# ReproAmp_V87_Stage_v0_1.net
KiCad netlist of a schematic drawn in Altium Designer
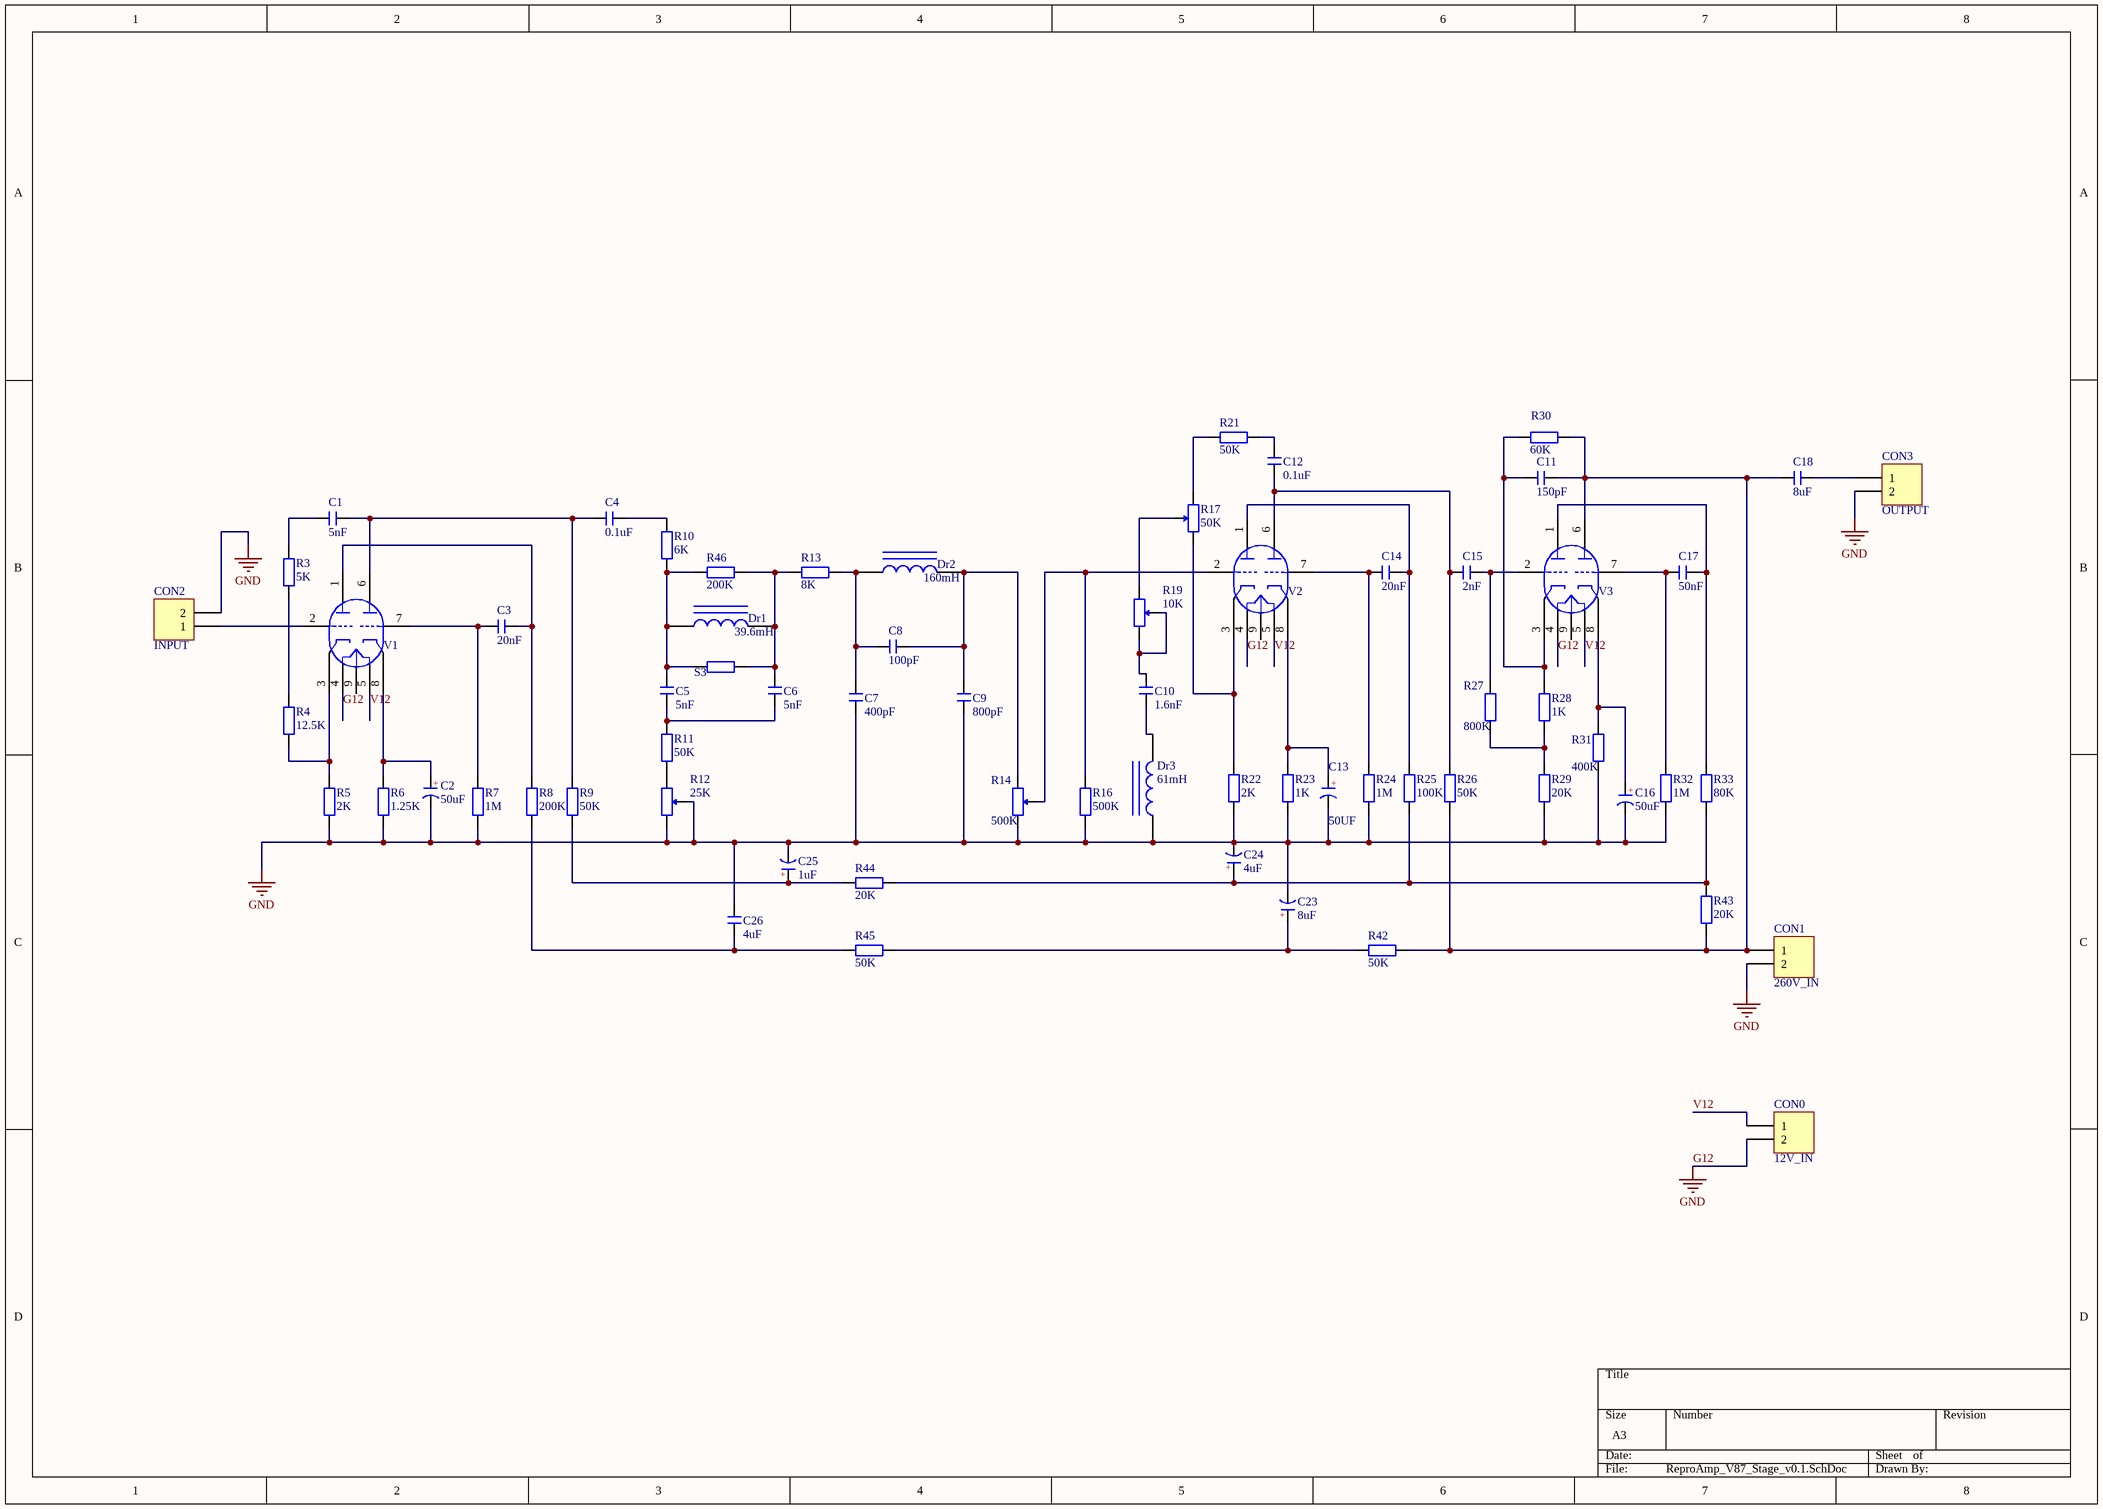
[diagram p0: ReproAmp_V87_Stage_v0.1.SchDoc]

(export (version "E")
  (design (tool "Eeschema 10.0.6"))
  (components
    (comp (ref "C1")
      (value "5nF")
      (footprint "CY 7.5*10*4")
      (description "CBB电容")
      (fields (field (name "版权归属") "源创客"))
      (libsource (lib "电阻-电容-电感") (part "C-CBB"))
    )
    (comp (ref "C2")
      (value "50uF")
      (footprint "CAP 5.0*12.5*20")
      (description "直插电解电容")
      (fields (field (name "版权归属") "源创客"))
      (libsource (lib "电阻-电容-电感") (part "C-CAP"))
    )
    (comp (ref "C3")
      (value "20nF")
      (footprint "CBB 10*12*8")
      (description "CBB电容")
      (fields (field (name "版权归属") "源创客"))
      (libsource (lib "电阻-电容-电感") (part "C-CBB"))
    )
    (comp (ref "C4")
      (value "0.1uF")
      (footprint "CBB 15*18*11")
      (description "CBB电容")
      (fields (field (name "版权归属") "源创客"))
      (libsource (lib "电阻-电容-电感") (part "C-CBB"))
    )
    (comp (ref "C5")
      (value "5nF")
      (footprint "CBB 7.2*7.2*13")
      (description "CBB电容")
      (fields (field (name "版权归属") "源创客"))
      (libsource (lib "电阻-电容-电感") (part "C-CBB"))
    )
    (comp (ref "C6")
      (value "5nF")
      (footprint "CBB 7.2*7.2*13")
      (description "CBB电容")
      (fields (field (name "版权归属") "源创客"))
      (libsource (lib "电阻-电容-电感") (part "C-CBB"))
    )
    (comp (ref "C7")
      (value "400pF")
      (footprint "CBB 7.2*7.2*13")
      (description "CBB电容")
      (fields (field (name "版权归属") "源创客"))
      (libsource (lib "电阻-电容-电感") (part "C-CBB"))
    )
    (comp (ref "C8")
      (value "100pF")
      (footprint "CBB 7.2*7.2*13")
      (description "CBB电容")
      (fields (field (name "版权归属") "源创客"))
      (libsource (lib "电阻-电容-电感") (part "C-CBB"))
    )
    (comp (ref "C9")
      (value "800pF")
      (footprint "CBB 7.2*7.2*13")
      (description "CBB电容")
      (fields (field (name "版权归属") "源创客"))
      (libsource (lib "电阻-电容-电感") (part "C-CBB"))
    )
    (comp (ref "C10")
      (value "1.6nF")
      (footprint "CBB 7.2*7.2*13")
      (description "CBB电容")
      (fields (field (name "版权归属") "源创客"))
      (libsource (lib "电阻-电容-电感") (part "C-CBB"))
    )
    (comp (ref "C11")
      (value "150pF")
      (footprint "CBB 15*18*11")
      (description "CBB电容")
      (fields (field (name "版权归属") "源创客"))
      (libsource (lib "电阻-电容-电感") (part "C-CBB"))
    )
    (comp (ref "C12")
      (value "0.1uF")
      (footprint "CBB 15*18*11")
      (description "CBB电容")
      (fields (field (name "版权归属") "源创客"))
      (libsource (lib "电阻-电容-电感") (part "C-CBB"))
    )
    (comp (ref "C13")
      (value "50UF")
      (footprint "CAP 5.0*12.5*20")
      (description "直插电解电容")
      (fields (field (name "版权归属") "源创客"))
      (libsource (lib "电阻-电容-电感") (part "C-CAP"))
    )
    (comp (ref "C14")
      (value "20nF")
      (footprint "CBB 10*12*8")
      (description "CBB电容")
      (fields (field (name "版权归属") "源创客"))
      (libsource (lib "电阻-电容-电感") (part "C-CBB"))
    )
    (comp (ref "C15")
      (value "2nF")
      (footprint "CY 7.5*8*4")
      (description "CBB电容")
      (fields (field (name "版权归属") "源创客"))
      (libsource (lib "电阻-电容-电感") (part "C-CBB"))
    )
    (comp (ref "C16")
      (value "50uF")
      (footprint "CAP 5.0*12.5*20")
      (description "直插电解电容")
      (fields (field (name "版权归属") "源创客"))
      (libsource (lib "电阻-电容-电感") (part "C-CAP"))
    )
    (comp (ref "C17")
      (value "50nF")
      (footprint "CBB 15*18*11")
      (description "CBB电容")
      (fields (field (name "版权归属") "源创客"))
      (libsource (lib "电阻-电容-电感") (part "C-CBB"))
    )
    (comp (ref "C18")
      (value "8uF")
      (footprint "CBB 50*30*30")
      (description "CBB电容")
      (fields (field (name "版权归属") "源创客"))
      (libsource (lib "电阻-电容-电感") (part "C-CBB"))
    )
    (comp (ref "C23")
      (value "8uF")
      (footprint "CAP 5.0*12.5*20")
      (description "直插电解电容")
      (fields (field (name "版权归属") "源创客"))
      (libsource (lib "电阻-电容-电感") (part "C-CAP"))
    )
    (comp (ref "C24")
      (value "4uF")
      (footprint "CAP 5.0*12.5*20")
      (description "直插电解电容")
      (fields (field (name "版权归属") "源创客"))
      (libsource (lib "电阻-电容-电感") (part "C-CAP"))
    )
    (comp (ref "C25")
      (value "1uF")
      (footprint "CAP 5.0*12.5*20")
      (description "直插电解电容")
      (fields (field (name "版权归属") "源创客"))
      (libsource (lib "电阻-电容-电感") (part "C-CAP"))
    )
    (comp (ref "C26")
      (value "4uF")
      (footprint "CBB 20*23*17")
      (description "CBB电容")
      (fields (field (name "版权归属") "源创客"))
      (libsource (lib "电阻-电容-电感") (part "C-CBB"))
    )
    (comp (ref "CON0")
      (value "12V_IN")
      (footprint "HX5.08-2L")
      (libsource (lib "Connectors") (part "EDG5.08-2P"))
    )
    (comp (ref "CON1")
      (value "260V_IN")
      (footprint "HX5.08-2L")
      (libsource (lib "Connectors") (part "EDG5.08-2P"))
    )
    (comp (ref "CON2") (value "INPUT") (footprint "HX5.08-2L") (libsource (lib "") (part "EDG5.08-2P_1")))
    (comp (ref "CON3")
      (value "OUTPUT")
      (footprint "HX5.08-2L")
      (libsource (lib "Connectors") (part "EDG5.08-2P"))
    )
    (comp (ref "Dr1")
      (value "39.6mH")
      (footprint "AXIAL-0.5")
      (description "Magnetic-Core Inductor")
      (fields (field (name "PUBLISHER") "Altium Limited"))
      (libsource (lib "Miscellaneous Devices") (part "Inductor Iron"))
    )
    (comp (ref "Dr2")
      (value "160mH")
      (footprint "AXIAL-0.5")
      (description "Magnetic-Core Inductor")
      (fields (field (name "PUBLISHER") "Altium Limited"))
      (libsource (lib "Miscellaneous Devices") (part "Inductor Iron"))
    )
    (comp (ref "Dr3")
      (value "61mH")
      (footprint "AXIAL-0.5")
      (description "Magnetic-Core Inductor")
      (fields (field (name "PUBLISHER") "Altium Limited"))
      (libsource (lib "Miscellaneous Devices") (part "Inductor Iron"))
    )
    (comp (ref "R3")
      (value "5K")
      (footprint "RS 1W")
      (description "直插色环电阻")
      (fields (field (name "版权归属") "源创客"))
      (libsource (lib "电阻-电容-电感") (part "R-CRR"))
    )
    (comp (ref "R4")
      (value "12.5K")
      (footprint "RS 1W")
      (description "直插色环电阻")
      (fields (field (name "版权归属") "源创客"))
      (libsource (lib "电阻-电容-电感") (part "R-CRR"))
    )
    (comp (ref "R5")
      (value "2K")
      (footprint "RS 1W")
      (description "直插色环电阻")
      (fields (field (name "版权归属") "源创客"))
      (libsource (lib "电阻-电容-电感") (part "R-CRR"))
    )
    (comp (ref "R6")
      (value "1.25K")
      (footprint "RS 1W")
      (description "直插色环电阻")
      (fields (field (name "版权归属") "源创客"))
      (libsource (lib "电阻-电容-电感") (part "R-CRR"))
    )
    (comp (ref "R7")
      (value "1M")
      (footprint "RS 1W")
      (description "直插色环电阻")
      (fields (field (name "版权归属") "源创客"))
      (libsource (lib "电阻-电容-电感") (part "R-CRR"))
    )
    (comp (ref "R8")
      (value "200K")
      (footprint "RS 1W")
      (description "直插色环电阻")
      (fields (field (name "版权归属") "源创客"))
      (libsource (lib "电阻-电容-电感") (part "R-CRR"))
    )
    (comp (ref "R9")
      (value "50K")
      (footprint "RS 2W")
      (description "直插色环电阻")
      (fields (field (name "版权归属") "源创客"))
      (libsource (lib "电阻-电容-电感") (part "R-CRR"))
    )
    (comp (ref "R10")
      (value "6K")
      (footprint "RS 1/2W")
      (description "直插色环电阻")
      (fields (field (name "版权归属") "源创客"))
      (libsource (lib "电阻-电容-电感") (part "R-CRR"))
    )
    (comp (ref "R11")
      (value "50K")
      (footprint "RS 1/2W")
      (description "直插色环电阻")
      (fields (field (name "版权归属") "源创客"))
      (libsource (lib "电阻-电容-电感") (part "R-CRR"))
    )
    (comp (ref "R12")
      (value "25K")
      (footprint "RS 1/2W-VR")
      (description "直插可调电阻-顶调")
      (libsource (lib "电阻-电容-电感") (part "VR-W"))
    )
    (comp (ref "R13")
      (value "8K")
      (footprint "RS 1/2W")
      (description "直插色环电阻")
      (fields (field (name "版权归属") "源创客"))
      (libsource (lib "电阻-电容-电感") (part "R-CRR"))
    )
    (comp (ref "R14")
      (value "500K")
      (footprint "RS 1/2W-VR")
      (description "直插可调电阻-顶调")
      (libsource (lib "电阻-电容-电感") (part "VR-W"))
    )
    (comp (ref "R16")
      (value "500K")
      (footprint "RS 1W")
      (description "直插色环电阻")
      (fields (field (name "版权归属") "源创客"))
      (libsource (lib "电阻-电容-电感") (part "R-CRR"))
    )
    (comp (ref "R17")
      (value "50K")
      (footprint "RS 1/2W-VR")
      (description "直插可调电阻-顶调")
      (libsource (lib "电阻-电容-电感") (part "VR-W"))
    )
    (comp (ref "R19")
      (value "10K")
      (footprint "RS 1/2W-VR")
      (description "直插可调电阻-顶调")
      (libsource (lib "电阻-电容-电感") (part "VR-W"))
    )
    (comp (ref "R21")
      (value "50K")
      (footprint "RS 1W")
      (description "直插色环电阻")
      (fields (field (name "版权归属") "源创客"))
      (libsource (lib "电阻-电容-电感") (part "R-CRR"))
    )
    (comp (ref "R22")
      (value "2K")
      (footprint "RS 1W")
      (description "直插色环电阻")
      (fields (field (name "版权归属") "源创客"))
      (libsource (lib "电阻-电容-电感") (part "R-CRR"))
    )
    (comp (ref "R23")
      (value "1K")
      (footprint "RS 1W")
      (description "直插色环电阻")
      (fields (field (name "版权归属") "源创客"))
      (libsource (lib "电阻-电容-电感") (part "R-CRR"))
    )
    (comp (ref "R24")
      (value "1M")
      (footprint "RS 1W")
      (description "直插色环电阻")
      (fields (field (name "版权归属") "源创客"))
      (libsource (lib "电阻-电容-电感") (part "R-CRR"))
    )
    (comp (ref "R25")
      (value "100K")
      (footprint "RS 2W")
      (description "直插色环电阻")
      (fields (field (name "版权归属") "源创客"))
      (libsource (lib "电阻-电容-电感") (part "R-CRR"))
    )
    (comp (ref "R26")
      (value "50K")
      (footprint "RS 1W")
      (description "直插色环电阻")
      (fields (field (name "版权归属") "源创客"))
      (libsource (lib "电阻-电容-电感") (part "R-CRR"))
    )
    (comp (ref "R27")
      (value "800K")
      (footprint "RS 1W")
      (description "直插色环电阻")
      (fields (field (name "版权归属") "源创客"))
      (libsource (lib "电阻-电容-电感") (part "R-CRR"))
    )
    (comp (ref "R28")
      (value "1K")
      (footprint "RS 1W")
      (description "直插色环电阻")
      (fields (field (name "版权归属") "源创客"))
      (libsource (lib "电阻-电容-电感") (part "R-CRR"))
    )
    (comp (ref "R29")
      (value "20K")
      (footprint "RS 1W")
      (description "直插色环电阻")
      (fields (field (name "版权归属") "源创客"))
      (libsource (lib "电阻-电容-电感") (part "R-CRR"))
    )
    (comp (ref "R30")
      (value "60K")
      (footprint "RS 1W")
      (description "直插色环电阻")
      (fields (field (name "版权归属") "源创客"))
      (libsource (lib "电阻-电容-电感") (part "R-CRR"))
    )
    (comp (ref "R31")
      (value "400K")
      (footprint "RS 1W")
      (description "直插色环电阻")
      (fields (field (name "版权归属") "源创客"))
      (libsource (lib "电阻-电容-电感") (part "R-CRR"))
    )
    (comp (ref "R32")
      (value "1M")
      (footprint "RS 1W")
      (description "直插色环电阻")
      (fields (field (name "版权归属") "源创客"))
      (libsource (lib "电阻-电容-电感") (part "R-CRR"))
    )
    (comp (ref "R33")
      (value "80K")
      (footprint "RS 2W")
      (description "直插色环电阻")
      (fields (field (name "版权归属") "源创客"))
      (libsource (lib "电阻-电容-电感") (part "R-CRR"))
    )
    (comp (ref "R42")
      (value "50K")
      (footprint "RS 1W")
      (description "直插色环电阻")
      (fields (field (name "版权归属") "源创客"))
      (libsource (lib "电阻-电容-电感") (part "R-CRR"))
    )
    (comp (ref "R43")
      (value "20K")
      (footprint "RS 1W")
      (description "直插色环电阻")
      (fields (field (name "版权归属") "源创客"))
      (libsource (lib "电阻-电容-电感") (part "R-CRR"))
    )
    (comp (ref "R44")
      (value "20K")
      (footprint "RS 1W")
      (description "直插色环电阻")
      (fields (field (name "版权归属") "源创客"))
      (libsource (lib "电阻-电容-电感") (part "R-CRR"))
    )
    (comp (ref "R45")
      (value "50K")
      (footprint "RS 1W")
      (description "直插色环电阻")
      (fields (field (name "版权归属") "源创客"))
      (libsource (lib "电阻-电容-电感") (part "R-CRR"))
    )
    (comp (ref "R46")
      (value "200K")
      (footprint "RS 1/2W")
      (description "直插色环电阻")
      (fields (field (name "版权归属") "源创客"))
      (libsource (lib "电阻-电容-电感") (part "R-CRR"))
    )
    (comp (ref "S3")
      (value "0")
      (footprint "RS 1/2W")
      (description "直插色环电阻")
      (fields (field (name "版权归属") "源创客"))
      (libsource (lib "电阻-电容-电感") (part "R-CRR"))
    )
    (comp (ref "V1")
      (value "Tube E80CC")
      (footprint "VTUBE-9")
      (description "High Mu Dual Triode")
      (fields (field (name "PUBLISHER") "Altium Limited"))
      (libsource (lib "Miscellaneous Devices") (part "Tube 12AX7"))
    )
    (comp (ref "V2")
      (value "Tube E80CC")
      (footprint "VTUBE-9")
      (description "High Mu Dual Triode")
      (fields (field (name "PUBLISHER") "Altium Limited"))
      (libsource (lib "Miscellaneous Devices") (part "Tube 12AX7"))
    )
    (comp (ref "V3")
      (value "Tube E80CC")
      (footprint "VTUBE-9")
      (description "High Mu Dual Triode")
      (fields (field (name "PUBLISHER") "Altium Limited"))
      (libsource (lib "Miscellaneous Devices") (part "Tube 12AX7"))
    )
  )
  (nets
    (net (code "1") (name "/V12") (class "Default")
      (node (ref "CON0") (pin "1") (pinfunction "1_1") (pintype "passive"))
      (node (ref "V1") (pin "5") (pinfunction "H_5") (pintype "passive"))
      (node (ref "V2") (pin "5") (pinfunction "H_5") (pintype "passive"))
      (node (ref "V3") (pin "5") (pinfunction "H_5") (pintype "passive"))
    )
    (net (code "2") (name "GND") (class "Default")
      (node (ref "C13") (pin "2") (pinfunction "K_2") (pintype "passive"))
      (node (ref "C16") (pin "2") (pinfunction "K_2") (pintype "passive"))
      (node (ref "C2") (pin "2") (pinfunction "K_2") (pintype "passive"))
      (node (ref "C23") (pin "2") (pinfunction "K_2") (pintype "passive"))
      (node (ref "C24") (pin "2") (pinfunction "K_2") (pintype "passive"))
      (node (ref "C25") (pin "2") (pinfunction "K_2") (pintype "passive"))
      (node (ref "C26") (pin "2") (pinfunction "2_2") (pintype "passive"))
      (node (ref "C7") (pin "1") (pinfunction "1_1") (pintype "passive"))
      (node (ref "C9") (pin "1") (pinfunction "1_1") (pintype "passive"))
      (node (ref "CON0") (pin "2") (pinfunction "2_2") (pintype "passive"))
      (node (ref "CON1") (pin "2") (pinfunction "2_2") (pintype "passive"))
      (node (ref "CON2") (pin "2") (pinfunction "2_2") (pintype "passive"))
      (node (ref "CON3") (pin "2") (pinfunction "2_2") (pintype "passive"))
      (node (ref "Dr3") (pin "1") (pinfunction "1_1") (pintype "passive"))
      (node (ref "R12") (pin "2") (pinfunction "2_2") (pintype "passive"))
      (node (ref "R12") (pin "3") (pinfunction "3_3") (pintype "passive"))
      (node (ref "R14") (pin "2") (pinfunction "2_2") (pintype "passive"))
      (node (ref "R16") (pin "1") (pinfunction "1_1") (pintype "passive"))
      (node (ref "R22") (pin "1") (pinfunction "1_1") (pintype "passive"))
      (node (ref "R23") (pin "1") (pinfunction "1_1") (pintype "passive"))
      (node (ref "R24") (pin "1") (pinfunction "1_1") (pintype "passive"))
      (node (ref "R29") (pin "1") (pinfunction "1_1") (pintype "passive"))
      (node (ref "R31") (pin "2") (pinfunction "2_2") (pintype "passive"))
      (node (ref "R32") (pin "2") (pinfunction "2_2") (pintype "passive"))
      (node (ref "R5") (pin "1") (pinfunction "1_1") (pintype "passive"))
      (node (ref "R6") (pin "1") (pinfunction "1_1") (pintype "passive"))
      (node (ref "R7") (pin "1") (pinfunction "1_1") (pintype "passive"))
      (node (ref "V1") (pin "4") (pinfunction "H_4") (pintype "passive"))
      (node (ref "V2") (pin "4") (pinfunction "H_4") (pintype "passive"))
      (node (ref "V3") (pin "4") (pinfunction "H_4") (pintype "passive"))
    )
    (net (code "3") (name "Net-(C1-Pad1)") (class "Default")
      (node (ref "C1") (pin "1") (pinfunction "1_1") (pintype "passive"))
      (node (ref "R3") (pin "2") (pinfunction "2_2") (pintype "passive"))
    )
    (net (code "4") (name "Net-(C2-A)") (class "Default")
      (node (ref "C2") (pin "1") (pinfunction "A_1") (pintype "passive"))
      (node (ref "R6") (pin "2") (pinfunction "2_2") (pintype "passive"))
      (node (ref "V1") (pin "8") (pinfunction "KT2_8") (pintype "passive"))
    )
    (net (code "5") (name "Net-(C4-Pad2)") (class "Default")
      (node (ref "C4") (pin "2") (pinfunction "2_2") (pintype "passive"))
      (node (ref "R10") (pin "2") (pinfunction "2_2") (pintype "passive"))
    )
    (net (code "6") (name "Net-(C5-Pad1)") (class "Default")
      (node (ref "C5") (pin "1") (pinfunction "1_1") (pintype "passive"))
      (node (ref "C6") (pin "1") (pinfunction "1_1") (pintype "passive"))
      (node (ref "R11") (pin "2") (pinfunction "2_2") (pintype "passive"))
    )
    (net (code "7") (name "Net-(C5-Pad2)") (class "Default")
      (node (ref "C5") (pin "2") (pinfunction "2_2") (pintype "passive"))
      (node (ref "Dr1") (pin "1") (pinfunction "1_1") (pintype "passive"))
      (node (ref "R10") (pin "1") (pinfunction "1_1") (pintype "passive"))
      (node (ref "R46") (pin "1") (pinfunction "1_1") (pintype "passive"))
      (node (ref "S3") (pin "1") (pinfunction "1_1") (pintype "passive"))
    )
    (net (code "8") (name "Net-(C6-Pad2)") (class "Default")
      (node (ref "C6") (pin "2") (pinfunction "2_2") (pintype "passive"))
      (node (ref "Dr1") (pin "2") (pinfunction "2_2") (pintype "passive"))
      (node (ref "R13") (pin "1") (pinfunction "1_1") (pintype "passive"))
      (node (ref "R46") (pin "2") (pinfunction "2_2") (pintype "passive"))
      (node (ref "S3") (pin "2") (pinfunction "2_2") (pintype "passive"))
    )
    (net (code "9") (name "Net-(C7-Pad2)") (class "Default")
      (node (ref "C7") (pin "2") (pinfunction "2_2") (pintype "passive"))
      (node (ref "C8") (pin "2") (pinfunction "2_2") (pintype "passive"))
      (node (ref "Dr2") (pin "1") (pinfunction "1_1") (pintype "passive"))
      (node (ref "R13") (pin "2") (pinfunction "2_2") (pintype "passive"))
    )
    (net (code "10") (name "Net-(C8-Pad1)") (class "Default")
      (node (ref "C8") (pin "1") (pinfunction "1_1") (pintype "passive"))
      (node (ref "C9") (pin "2") (pinfunction "2_2") (pintype "passive"))
      (node (ref "Dr2") (pin "2") (pinfunction "2_2") (pintype "passive"))
      (node (ref "R14") (pin "1") (pinfunction "1_1") (pintype "passive"))
    )
    (net (code "11") (name "Net-(C10-Pad1)") (class "Default")
      (node (ref "C10") (pin "1") (pinfunction "1_1") (pintype "passive"))
      (node (ref "Dr3") (pin "2") (pinfunction "2_2") (pintype "passive"))
    )
    (net (code "12") (name "Net-(C10-Pad2)") (class "Default")
      (node (ref "C10") (pin "2") (pinfunction "2_2") (pintype "passive"))
      (node (ref "R19") (pin "2") (pinfunction "2_2") (pintype "passive"))
      (node (ref "R19") (pin "3") (pinfunction "3_3") (pintype "passive"))
    )
    (net (code "13") (name "Net-(C12-Pad2)") (class "Default")
      (node (ref "C12") (pin "2") (pinfunction "2_2") (pintype "passive"))
      (node (ref "R21") (pin "2") (pinfunction "2_2") (pintype "passive"))
    )
    (net (code "14") (name "Net-(C13-A)") (class "Default")
      (node (ref "C13") (pin "1") (pinfunction "A_1") (pintype "passive"))
      (node (ref "R23") (pin "2") (pinfunction "2_2") (pintype "passive"))
      (node (ref "V2") (pin "8") (pinfunction "KT2_8") (pintype "passive"))
    )
    (net (code "15") (name "Net-(C16-A)") (class "Default")
      (node (ref "C16") (pin "1") (pinfunction "A_1") (pintype "passive"))
      (node (ref "R31") (pin "1") (pinfunction "1_1") (pintype "passive"))
      (node (ref "V3") (pin "8") (pinfunction "KT2_8") (pintype "passive"))
    )
    (net (code "16") (name "Net-(C18-Pad2)") (class "Default")
      (node (ref "C18") (pin "2") (pinfunction "2_2") (pintype "passive"))
      (node (ref "CON3") (pin "1") (pinfunction "1_1") (pintype "passive"))
    )
    (net (code "17") (name "Net-(C23-A)") (class "Default")
      (node (ref "C23") (pin "1") (pinfunction "A_1") (pintype "passive"))
      (node (ref "R42") (pin "1") (pinfunction "1_1") (pintype "passive"))
      (node (ref "R45") (pin "2") (pinfunction "2_2") (pintype "passive"))
    )
    (net (code "18") (name "Net-(C24-A)") (class "Default")
      (node (ref "C24") (pin "1") (pinfunction "A_1") (pintype "passive"))
      (node (ref "R25") (pin "1") (pinfunction "1_1") (pintype "passive"))
      (node (ref "R33") (pin "2") (pinfunction "2_2") (pintype "passive"))
      (node (ref "R43") (pin "2") (pinfunction "2_2") (pintype "passive"))
      (node (ref "R44") (pin "2") (pinfunction "2_2") (pintype "passive"))
    )
    (net (code "19") (name "Net-(C25-A)") (class "Default")
      (node (ref "C25") (pin "1") (pinfunction "A_1") (pintype "passive"))
      (node (ref "R44") (pin "1") (pinfunction "1_1") (pintype "passive"))
      (node (ref "R9") (pin "1") (pinfunction "1_1") (pintype "passive"))
    )
    (net (code "20") (name "Net-(C26-Pad1)") (class "Default")
      (node (ref "C26") (pin "1") (pinfunction "1_1") (pintype "passive"))
      (node (ref "R45") (pin "1") (pinfunction "1_1") (pintype "passive"))
      (node (ref "R8") (pin "1") (pinfunction "1_1") (pintype "passive"))
    )
    (net (code "21") (name "Net-(R3-Pad1)") (class "Default")
      (node (ref "R3") (pin "1") (pinfunction "1_1") (pintype "passive"))
      (node (ref "R4") (pin "2") (pinfunction "2_2") (pintype "passive"))
    )
    (net (code "22") (name "Net-(R11-Pad1)") (class "Default")
      (node (ref "R11") (pin "1") (pinfunction "1_1") (pintype "passive"))
      (node (ref "R12") (pin "1") (pinfunction "1_1") (pintype "passive"))
    )
    (net (code "23") (name "Net-(R17-Pad1)") (class "Default")
      (node (ref "R17") (pin "1") (pinfunction "1_1") (pintype "passive"))
      (node (ref "R21") (pin "1") (pinfunction "1_1") (pintype "passive"))
    )
    (net (code "24") (name "Net-(R17-Pad3)") (class "Default")
      (node (ref "R17") (pin "3") (pinfunction "3_3") (pintype "passive"))
      (node (ref "R19") (pin "1") (pinfunction "1_1") (pintype "passive"))
    )
    (net (code "25") (name "Net-(R27-Pad1)") (class "Default")
      (node (ref "R27") (pin "1") (pinfunction "1_1") (pintype "passive"))
      (node (ref "R28") (pin "1") (pinfunction "1_1") (pintype "passive"))
      (node (ref "R29") (pin "2") (pinfunction "2_2") (pintype "passive"))
    )
    (net (code "26") (name "Net-(V1-GT1)") (class "Default")
      (node (ref "CON2") (pin "1") (pinfunction "1_1") (pintype "passive"))
      (node (ref "V1") (pin "2") (pinfunction "GT1_2") (pintype "passive"))
    )
    (net (code "27") (name "Net-(V1-GT2)") (class "Default")
      (node (ref "C3") (pin "1") (pinfunction "1_1") (pintype "passive"))
      (node (ref "R7") (pin "2") (pinfunction "2_2") (pintype "passive"))
      (node (ref "V1") (pin "7") (pinfunction "GT2_7") (pintype "passive"))
    )
    (net (code "28") (name "Net-(V1-KT1)") (class "Default")
      (node (ref "R4") (pin "1") (pinfunction "1_1") (pintype "passive"))
      (node (ref "R5") (pin "2") (pinfunction "2_2") (pintype "passive"))
      (node (ref "V1") (pin "3") (pinfunction "KT1_3") (pintype "passive"))
    )
    (net (code "29") (name "Net-(V1-PT1)") (class "Default")
      (node (ref "C3") (pin "2") (pinfunction "2_2") (pintype "passive"))
      (node (ref "R8") (pin "2") (pinfunction "2_2") (pintype "passive"))
      (node (ref "V1") (pin "1") (pinfunction "PT1_1") (pintype "passive"))
    )
    (net (code "30") (name "Net-(V1-PT2)") (class "Default")
      (node (ref "C1") (pin "2") (pinfunction "2_2") (pintype "passive"))
      (node (ref "C4") (pin "1") (pinfunction "1_1") (pintype "passive"))
      (node (ref "R9") (pin "2") (pinfunction "2_2") (pintype "passive"))
      (node (ref "V1") (pin "6") (pinfunction "PT2_6") (pintype "passive"))
    )
    (net (code "31") (name "Net-(V2-GT1)") (class "Default")
      (node (ref "R14") (pin "3") (pinfunction "3_3") (pintype "passive"))
      (node (ref "R16") (pin "2") (pinfunction "2_2") (pintype "passive"))
      (node (ref "V2") (pin "2") (pinfunction "GT1_2") (pintype "passive"))
    )
    (net (code "32") (name "Net-(V2-GT2)") (class "Default")
      (node (ref "C14") (pin "1") (pinfunction "1_1") (pintype "passive"))
      (node (ref "R24") (pin "2") (pinfunction "2_2") (pintype "passive"))
      (node (ref "V2") (pin "7") (pinfunction "GT2_7") (pintype "passive"))
    )
    (net (code "33") (name "Net-(V2-KT1)") (class "Default")
      (node (ref "R17") (pin "2") (pinfunction "2_2") (pintype "passive"))
      (node (ref "R22") (pin "2") (pinfunction "2_2") (pintype "passive"))
      (node (ref "V2") (pin "3") (pinfunction "KT1_3") (pintype "passive"))
    )
    (net (code "34") (name "Net-(V2-PT1)") (class "Default")
      (node (ref "C14") (pin "2") (pinfunction "2_2") (pintype "passive"))
      (node (ref "R25") (pin "2") (pinfunction "2_2") (pintype "passive"))
      (node (ref "V2") (pin "1") (pinfunction "PT1_1") (pintype "passive"))
    )
    (net (code "35") (name "Net-(V2-PT2)") (class "Default")
      (node (ref "C12") (pin "1") (pinfunction "1_1") (pintype "passive"))
      (node (ref "C15") (pin "1") (pinfunction "1_1") (pintype "passive"))
      (node (ref "R26") (pin "2") (pinfunction "2_2") (pintype "passive"))
      (node (ref "V2") (pin "6") (pinfunction "PT2_6") (pintype "passive"))
    )
    (net (code "36") (name "Net-(V3-GT1)") (class "Default")
      (node (ref "C15") (pin "2") (pinfunction "2_2") (pintype "passive"))
      (node (ref "R27") (pin "2") (pinfunction "2_2") (pintype "passive"))
      (node (ref "V3") (pin "2") (pinfunction "GT1_2") (pintype "passive"))
    )
    (net (code "37") (name "Net-(V3-GT2)") (class "Default")
      (node (ref "C17") (pin "1") (pinfunction "1_1") (pintype "passive"))
      (node (ref "R32") (pin "1") (pinfunction "1_1") (pintype "passive"))
      (node (ref "V3") (pin "7") (pinfunction "GT2_7") (pintype "passive"))
    )
    (net (code "38") (name "Net-(V3-KT1)") (class "Default")
      (node (ref "C11") (pin "1") (pinfunction "1_1") (pintype "passive"))
      (node (ref "R28") (pin "2") (pinfunction "2_2") (pintype "passive"))
      (node (ref "R30") (pin "2") (pinfunction "2_2") (pintype "passive"))
      (node (ref "V3") (pin "3") (pinfunction "KT1_3") (pintype "passive"))
    )
    (net (code "39") (name "Net-(V3-PT1)") (class "Default")
      (node (ref "C17") (pin "2") (pinfunction "2_2") (pintype "passive"))
      (node (ref "R33") (pin "1") (pinfunction "1_1") (pintype "passive"))
      (node (ref "V3") (pin "1") (pinfunction "PT1_1") (pintype "passive"))
    )
    (net (code "40") (name "Net-(V3-PT2)") (class "Default")
      (node (ref "C11") (pin "2") (pinfunction "2_2") (pintype "passive"))
      (node (ref "C18") (pin "1") (pinfunction "1_1") (pintype "passive"))
      (node (ref "CON1") (pin "1") (pinfunction "1_1") (pintype "passive"))
      (node (ref "R26") (pin "1") (pinfunction "1_1") (pintype "passive"))
      (node (ref "R30") (pin "1") (pinfunction "1_1") (pintype "passive"))
      (node (ref "R42") (pin "2") (pinfunction "2_2") (pintype "passive"))
      (node (ref "R43") (pin "1") (pinfunction "1_1") (pintype "passive"))
      (node (ref "V3") (pin "6") (pinfunction "PT2_6") (pintype "passive"))
    )
    (net (code "41") (name "unconnected-(V1-HM-Pad9)") (class "Default")
      (node (ref "V1") (pin "9") (pinfunction "HM_9") (pintype "passive"))
    )
    (net (code "42") (name "unconnected-(V2-HM-Pad9)") (class "Default")
      (node (ref "V2") (pin "9") (pinfunction "HM_9") (pintype "passive"))
    )
    (net (code "43") (name "unconnected-(V3-HM-Pad9)") (class "Default")
      (node (ref "V3") (pin "9") (pinfunction "HM_9") (pintype "passive"))
    )
  )
)
